# SD_Card.net
KiCad netlist of a schematic drawn in Altium Designer
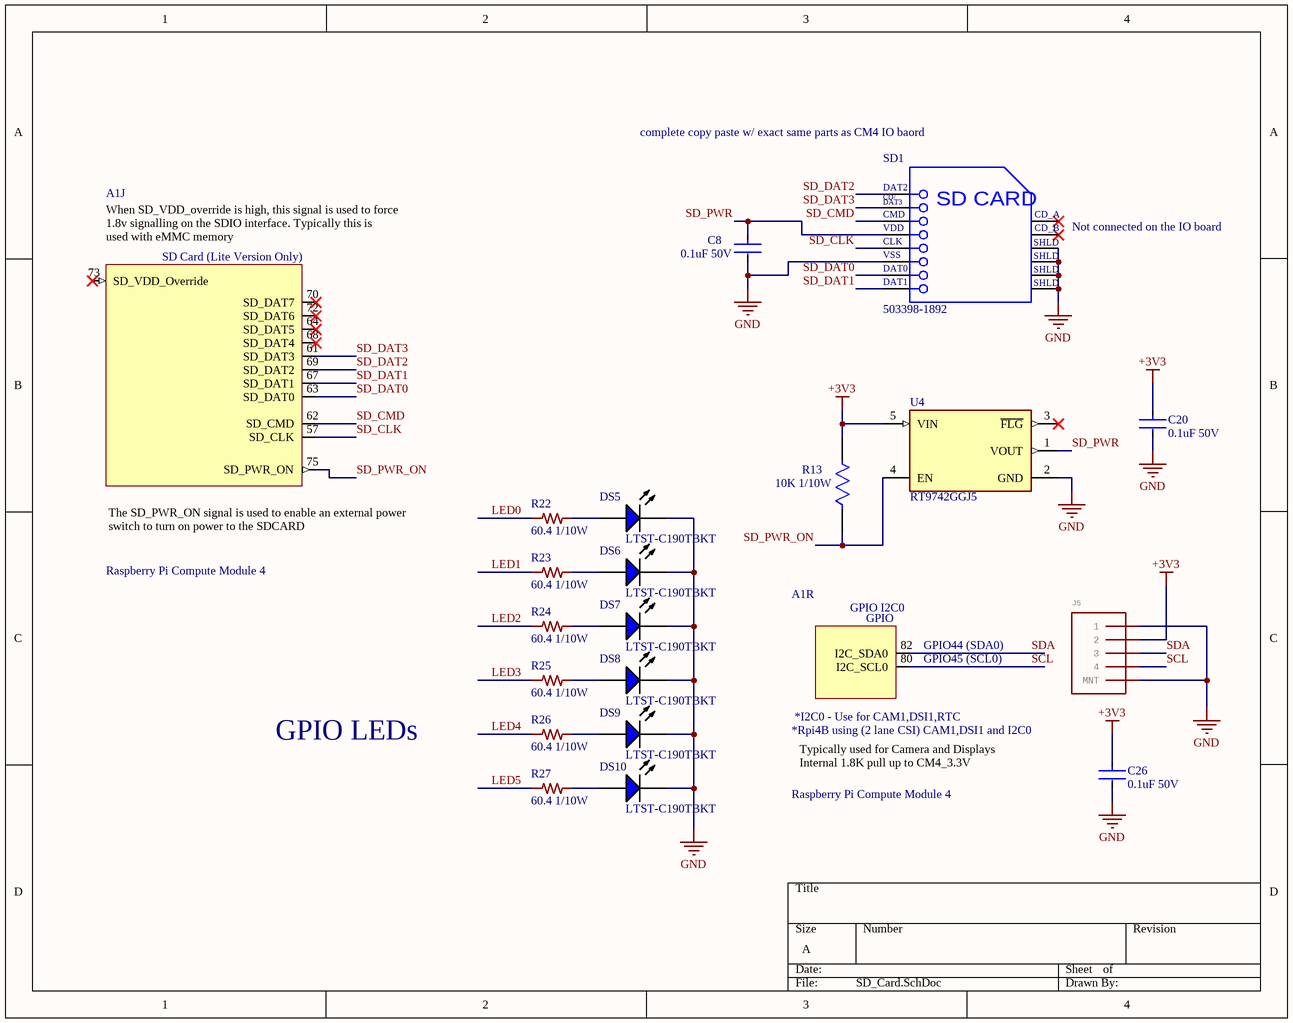
[diagram p0: SD_Card.SchDoc]

(export (version "E")
  (design (tool "Eeschema 10.0.6"))
  (components
    (comp (ref "A1")
      (value "Raspberry Pi Compute Module 4")
      (footprint "CM4-F40C-100DS-0.4v_1.5mm_0mm")
      (description "Raspberry Pi Compute Module 4 by Amornthep Phunsin")
      (libsource (lib "CM4") (part "CM4"))
    )
    (comp (ref "C8")
      (value "0.1uF 50V")
      (footprint "CAPACITOR_0603")
      (description "CAP CER 0.1UF 50V X7R 0603")
      (fields (field (name "MFR") "Samsung Electro-Mechanics") (field (name "MPN") "CL10B104KB8NNWC"))
      (libsource (lib "CM4") (part "CL10B104KB8NNWC"))
    )
    (comp (ref "C20")
      (value "0.1uF 50V")
      (footprint "CAPACITOR_0603")
      (description "CAP CER 0.1UF 50V X7R 0603")
      (fields (field (name "MFR") "Samsung Electro-Mechanics") (field (name "MPN") "CL10B104KB8NNWC"))
      (libsource (lib "CM4") (part "CL10B104KB8NNWC"))
    )
    (comp (ref "C26")
      (value "0.1uF 50V")
      (footprint "CAPACITOR_0603")
      (description "CAP CER 0.1UF 50V X7R 0603")
      (fields (field (name "MFR") "Samsung Electro-Mechanics") (field (name "MPN") "CL10B104KB8NNWC"))
      (libsource (lib "CM4") (part "CL10B104KB8NNWC"))
    )
    (comp (ref "DS5")
      (value "LTST-C190TBKT")
      (footprint "LTST-C190TBKT-2_V")
      (description "LED Uni-Color Blue, 76 mW, 20 mA, -20 to 80 degC, 2-Pin SMD, RoHS, Tape and Reel")
      (fields (field (name "MFR") "Lite-On"))
      (libsource (lib "CM4") (part "LTST-C190TBKT"))
    )
    (comp (ref "DS6")
      (value "LTST-C190TBKT")
      (footprint "LTST-C190TBKT-2_V")
      (description "LED Uni-Color Blue, 76 mW, 20 mA, -20 to 80 degC, 2-Pin SMD, RoHS, Tape and Reel")
      (fields (field (name "MFR") "Lite-On"))
      (libsource (lib "CM4") (part "LTST-C190TBKT"))
    )
    (comp (ref "DS7")
      (value "LTST-C190TBKT")
      (footprint "LTST-C190TBKT-2_V")
      (description "LED Uni-Color Blue, 76 mW, 20 mA, -20 to 80 degC, 2-Pin SMD, RoHS, Tape and Reel")
      (fields (field (name "MFR") "Lite-On"))
      (libsource (lib "CM4") (part "LTST-C190TBKT"))
    )
    (comp (ref "DS8")
      (value "LTST-C190TBKT")
      (footprint "LTST-C190TBKT-2_V")
      (description "LED Uni-Color Blue, 76 mW, 20 mA, -20 to 80 degC, 2-Pin SMD, RoHS, Tape and Reel")
      (fields (field (name "MFR") "Lite-On"))
      (libsource (lib "CM4") (part "LTST-C190TBKT"))
    )
    (comp (ref "DS9")
      (value "LTST-C190TBKT")
      (footprint "LTST-C190TBKT-2_V")
      (description "LED Uni-Color Blue, 76 mW, 20 mA, -20 to 80 degC, 2-Pin SMD, RoHS, Tape and Reel")
      (fields (field (name "MFR") "Lite-On"))
      (libsource (lib "CM4") (part "LTST-C190TBKT"))
    )
    (comp (ref "DS10")
      (value "LTST-C190TBKT")
      (footprint "LTST-C190TBKT-2_V")
      (description "LED Uni-Color Blue, 76 mW, 20 mA, -20 to 80 degC, 2-Pin SMD, RoHS, Tape and Reel")
      (fields (field (name "MFR") "Lite-On"))
      (libsource (lib "CM4") (part "LTST-C190TBKT"))
    )
    (comp (ref "J5")
      (value "4 Pin Connector")
      (footprint "JST_SM04B-SRSS-TB(LF)(SN)")
      (description "CONN HEADER SMD R/A 4POS 1MM")
      (fields (field (name "MANUFACTURER") "JST") (field (name "MPN") "SM04B-SRSS-TB"))
      (libsource (lib "CM4") (part "CONNECTOR-4_?_*JST_SR_R/A"))
    )
    (comp (ref "R13")
      (value "10K 1/10W")
      (footprint "0603R")
      (description "RES SMD 10K OHM 1% 1/10W 0603")
      (fields (field (name "MFR") "Parasonic") (field (name "MPN") "ERJ-3EKF1002V"))
      (libsource (lib "CM4") (part "ERJ-3EKF1002V"))
    )
    (comp (ref "R22")
      (value "60.4 1/10W")
      (footprint "0603R")
      (description "RES SMD 60.4 OHM 1% 1/10W 0603")
      (fields (field (name "MANUFACTURER") "Stackpole Electronics Inc") (field (name "MPN") "RMCF0603FT60R4"))
      (libsource (lib "CM4") (part "RMCF0603FT60R4"))
    )
    (comp (ref "R23")
      (value "60.4 1/10W")
      (footprint "0603R")
      (description "RES SMD 60.4 OHM 1% 1/10W 0603")
      (fields (field (name "MANUFACTURER") "Stackpole Electronics Inc") (field (name "MPN") "RMCF0603FT60R4"))
      (libsource (lib "CM4") (part "RMCF0603FT60R4"))
    )
    (comp (ref "R24")
      (value "60.4 1/10W")
      (footprint "0603R")
      (description "RES SMD 60.4 OHM 1% 1/10W 0603")
      (fields (field (name "MANUFACTURER") "Stackpole Electronics Inc") (field (name "MPN") "RMCF0603FT60R4"))
      (libsource (lib "CM4") (part "RMCF0603FT60R4"))
    )
    (comp (ref "R25")
      (value "60.4 1/10W")
      (footprint "0603R")
      (description "RES SMD 60.4 OHM 1% 1/10W 0603")
      (fields (field (name "MANUFACTURER") "Stackpole Electronics Inc") (field (name "MPN") "RMCF0603FT60R4"))
      (libsource (lib "CM4") (part "RMCF0603FT60R4"))
    )
    (comp (ref "R26")
      (value "60.4 1/10W")
      (footprint "0603R")
      (description "RES SMD 60.4 OHM 1% 1/10W 0603")
      (fields (field (name "MANUFACTURER") "Stackpole Electronics Inc") (field (name "MPN") "RMCF0603FT60R4"))
      (libsource (lib "CM4") (part "RMCF0603FT60R4"))
    )
    (comp (ref "R27")
      (value "60.4 1/10W")
      (footprint "0603R")
      (description "RES SMD 60.4 OHM 1% 1/10W 0603")
      (fields (field (name "MANUFACTURER") "Stackpole Electronics Inc") (field (name "MPN") "RMCF0603FT60R4"))
      (libsource (lib "CM4") (part "RMCF0603FT60R4"))
    )
    (comp (ref "SD1")
      (value "503398-1892")
      (footprint "MOLX-503398-1892_V")
      (description "Micro SD Connector, Pitch 1.1 mm, 8 Position, Height 1.4 mm, -25 to 85 degC, RoHS, Tape and Reel")
      (fields (field (name "MFR") "Molex"))
      (libsource (lib "CM4") (part "503398-1892"))
    )
    (comp (ref "U4")
      (value "RT9742GGJ5")
      (footprint "FP-RT9742GGJ5-IPC_C")
      (description "IC PWR SWTCH N-CHAN 1:1 TSOT23-5")
      (fields (field (name "MFR") "Richtek USA Inc."))
      (libsource (lib "Altium Content Vault") (part "6b3db7b45087fee8fb60b49bef92a32"))
    )
  )
  (nets
    (net (code "1") (name "+3V3") (class "Default")
      (node (ref "C20") (pin "2") (pinfunction "2_2") (pintype "passive"))
      (node (ref "C26") (pin "2") (pinfunction "2_2") (pintype "passive"))
      (node (ref "J5") (pin "2") (pinfunction "2_2") (pintype "passive"))
      (node (ref "R13") (pin "2") (pinfunction "2_2") (pintype "passive"))
      (node (ref "U4") (pin "5") (pinfunction "VIN_5") (pintype "input"))
    )
    (net (code "2") (name "/LED0") (class "Default")
      (node (ref "R22") (pin "1") (pinfunction "1_1") (pintype "passive"))
    )
    (net (code "3") (name "/LED1") (class "Default")
      (node (ref "R23") (pin "1") (pinfunction "1_1") (pintype "passive"))
    )
    (net (code "4") (name "/LED2") (class "Default")
      (node (ref "R24") (pin "1") (pinfunction "1_1") (pintype "passive"))
    )
    (net (code "5") (name "/LED3") (class "Default")
      (node (ref "R25") (pin "1") (pinfunction "1_1") (pintype "passive"))
    )
    (net (code "6") (name "/LED4") (class "Default")
      (node (ref "R26") (pin "1") (pinfunction "1_1") (pintype "passive"))
    )
    (net (code "7") (name "/LED5") (class "Default")
      (node (ref "R27") (pin "1") (pinfunction "1_1") (pintype "passive"))
    )
    (net (code "8") (name "/SCL") (class "Default")
      (node (ref "A1") (pin "80") (pinfunction "I2C_SCL0_80") (pintype "passive"))
      (node (ref "J5") (pin "4") (pinfunction "4_4") (pintype "passive"))
    )
    (net (code "9") (name "/SDA") (class "Default")
      (node (ref "A1") (pin "82") (pinfunction "I2C_SDA0_82") (pintype "passive"))
      (node (ref "J5") (pin "3") (pinfunction "3_3") (pintype "passive"))
    )
    (net (code "10") (name "/SD_CLK") (class "Default")
      (node (ref "A1") (pin "57") (pinfunction "SD_CLK_57") (pintype "passive"))
      (node (ref "SD1") (pin "5") (pinfunction "CLK_5") (pintype "passive"))
    )
    (net (code "11") (name "/SD_CMD") (class "Default")
      (node (ref "A1") (pin "62") (pinfunction "SD_CMD_62") (pintype "passive"))
      (node (ref "SD1") (pin "3") (pinfunction "CMD_3") (pintype "passive"))
    )
    (net (code "12") (name "/SD_DAT0") (class "Default")
      (node (ref "A1") (pin "63") (pinfunction "SD_DAT0_63") (pintype "passive"))
      (node (ref "SD1") (pin "7") (pinfunction "DAT0_7") (pintype "passive"))
    )
    (net (code "13") (name "/SD_DAT1") (class "Default")
      (node (ref "A1") (pin "67") (pinfunction "SD_DAT1_67") (pintype "passive"))
      (node (ref "SD1") (pin "8") (pinfunction "DAT1_8") (pintype "passive"))
    )
    (net (code "14") (name "/SD_DAT2") (class "Default")
      (node (ref "A1") (pin "69") (pinfunction "SD_DAT2_69") (pintype "passive"))
      (node (ref "SD1") (pin "1") (pinfunction "DAT2_1") (pintype "passive"))
    )
    (net (code "15") (name "/SD_DAT3") (class "Default")
      (node (ref "A1") (pin "61") (pinfunction "SD_DAT3_61") (pintype "passive"))
      (node (ref "SD1") (pin "2") (pinfunction "CD/DAT3_2") (pintype "passive"))
    )
    (net (code "16") (name "/SD_PWR") (class "Default")
      (node (ref "C8") (pin "2") (pinfunction "2_2") (pintype "passive"))
      (node (ref "SD1") (pin "4") (pinfunction "VDD_4") (pintype "passive"))
      (node (ref "U4") (pin "1") (pinfunction "VOUT_1") (pintype "output"))
    )
    (net (code "17") (name "/SD_PWR_ON") (class "Default")
      (node (ref "A1") (pin "75") (pinfunction "SD_PWR_ON_75") (pintype "output"))
      (node (ref "R13") (pin "1") (pinfunction "1_1") (pintype "passive"))
      (node (ref "U4") (pin "4") (pinfunction "EN_4") (pintype "passive"))
    )
    (net (code "18") (name "GND") (class "Default")
      (node (ref "C20") (pin "1") (pinfunction "1_1") (pintype "passive"))
      (node (ref "C26") (pin "1") (pinfunction "1_1") (pintype "passive"))
      (node (ref "C8") (pin "1") (pinfunction "1_1") (pintype "passive"))
      (node (ref "DS10") (pin "2") (pinfunction "K_2") (pintype "passive"))
      (node (ref "DS5") (pin "2") (pinfunction "K_2") (pintype "passive"))
      (node (ref "DS6") (pin "2") (pinfunction "K_2") (pintype "passive"))
      (node (ref "DS7") (pin "2") (pinfunction "K_2") (pintype "passive"))
      (node (ref "DS8") (pin "2") (pinfunction "K_2") (pintype "passive"))
      (node (ref "DS9") (pin "2") (pinfunction "K_2") (pintype "passive"))
      (node (ref "J5") (pin "0") (pinfunction "MNT_0") (pintype "passive"))
      (node (ref "J5") (pin "1") (pinfunction "1_1") (pintype "passive"))
      (node (ref "SD1") (pin "11") (pinfunction "SHLD_11") (pintype "passive"))
      (node (ref "SD1") (pin "12") (pinfunction "SHLD_12") (pintype "passive"))
      (node (ref "SD1") (pin "13") (pinfunction "SHLD_13") (pintype "passive"))
      (node (ref "SD1") (pin "14") (pinfunction "SHLD_14") (pintype "passive"))
      (node (ref "SD1") (pin "6") (pinfunction "VSS_6") (pintype "passive"))
      (node (ref "U4") (pin "2") (pinfunction "GND_2") (pintype "power_in"))
    )
    (net (code "19") (name "Net-(DS5-A)") (class "Default")
      (node (ref "DS5") (pin "1") (pinfunction "A_1") (pintype "passive"))
      (node (ref "R22") (pin "2") (pinfunction "2_2") (pintype "passive"))
    )
    (net (code "20") (name "Net-(DS6-A)") (class "Default")
      (node (ref "DS6") (pin "1") (pinfunction "A_1") (pintype "passive"))
      (node (ref "R23") (pin "2") (pinfunction "2_2") (pintype "passive"))
    )
    (net (code "21") (name "Net-(DS7-A)") (class "Default")
      (node (ref "DS7") (pin "1") (pinfunction "A_1") (pintype "passive"))
      (node (ref "R24") (pin "2") (pinfunction "2_2") (pintype "passive"))
    )
    (net (code "22") (name "Net-(DS8-A)") (class "Default")
      (node (ref "DS8") (pin "1") (pinfunction "A_1") (pintype "passive"))
      (node (ref "R25") (pin "2") (pinfunction "2_2") (pintype "passive"))
    )
    (net (code "23") (name "Net-(DS9-A)") (class "Default")
      (node (ref "DS9") (pin "1") (pinfunction "A_1") (pintype "passive"))
      (node (ref "R26") (pin "2") (pinfunction "2_2") (pintype "passive"))
    )
    (net (code "24") (name "Net-(DS10-A)") (class "Default")
      (node (ref "DS10") (pin "1") (pinfunction "A_1") (pintype "passive"))
      (node (ref "R27") (pin "2") (pinfunction "2_2") (pintype "passive"))
    )
    (net (code "25") (name "unconnected-(A1J-SD_DAT4-Pad68)") (class "Default")
      (node (ref "A1") (pin "68") (pinfunction "SD_DAT4_68") (pintype "passive+no_connect"))
    )
    (net (code "26") (name "unconnected-(A1J-SD_DAT5-Pad64)") (class "Default")
      (node (ref "A1") (pin "64") (pinfunction "SD_DAT5_64") (pintype "passive+no_connect"))
    )
    (net (code "27") (name "unconnected-(A1J-SD_DAT6-Pad72)") (class "Default")
      (node (ref "A1") (pin "72") (pinfunction "SD_DAT6_72") (pintype "passive+no_connect"))
    )
    (net (code "28") (name "unconnected-(A1J-SD_DAT7-Pad70)") (class "Default")
      (node (ref "A1") (pin "70") (pinfunction "SD_DAT7_70") (pintype "passive+no_connect"))
    )
    (net (code "29") (name "unconnected-(A1J-SD_VDD_Override-Pad73)") (class "Default")
      (node (ref "A1") (pin "73") (pinfunction "SD_VDD_Override_73") (pintype "input+no_connect"))
    )
    (net (code "30") (name "unconnected-(SD1-CD_A-Pad9)") (class "Default")
      (node (ref "SD1") (pin "9") (pinfunction "CD_A_9") (pintype "passive+no_connect"))
    )
    (net (code "31") (name "unconnected-(SD1-CD_B-Pad10)") (class "Default")
      (node (ref "SD1") (pin "10") (pinfunction "CD_B_10") (pintype "passive+no_connect"))
    )
    (net (code "32") (name "unconnected-(U4-~{FLG}-Pad3)") (class "Default")
      (node (ref "U4") (pin "3") (pinfunction "~{FLG}_3") (pintype "output+no_connect"))
    )
  )
)
